# nucleo_jlink.net
KiCad netlist of a schematic drawn in EAGLE
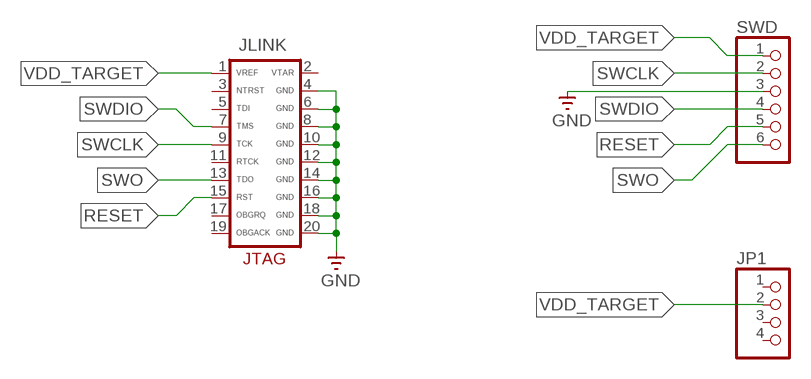
[diagram p0: schematic, sheet 1]

(export (version "E")
  (design (tool "Eeschema 10.0.6"))
  (components
    (comp (ref "JLINK")
      (value "JTAG-ARM")
      (footprint "eagle-import:JTAG-ARM")
      (libsource (lib "eagle-import") (part "JTAG-ARM"))
    )
    (comp (ref "JP1")
      (value "PINHD-1X4")
      (footprint "eagle-import:1X04")
      (libsource (lib "eagle-import") (part "PINHD-1X4"))
    )
    (comp (ref "SWD")
      (value "PINHD-1X6")
      (footprint "eagle-import:1X06")
      (libsource (lib "eagle-import") (part "PINHD-1X6"))
    )
  )
  (nets
    (net (code "1") (name "GND") (class "Default")
      (node (ref "JLINK") (pin "10") (pinfunction "GND_10") (pintype "passive"))
      (node (ref "JLINK") (pin "12") (pinfunction "GND_12") (pintype "passive"))
      (node (ref "JLINK") (pin "14") (pinfunction "GND_14") (pintype "passive"))
      (node (ref "JLINK") (pin "16") (pinfunction "GND_16") (pintype "passive"))
      (node (ref "JLINK") (pin "18") (pinfunction "GND_18") (pintype "passive"))
      (node (ref "JLINK") (pin "20") (pinfunction "GND_20") (pintype "passive"))
      (node (ref "JLINK") (pin "4") (pinfunction "GND_4") (pintype "passive"))
      (node (ref "JLINK") (pin "6") (pinfunction "GND_6") (pintype "passive"))
      (node (ref "JLINK") (pin "8") (pinfunction "GND_8") (pintype "passive"))
      (node (ref "SWD") (pin "3") (pinfunction "3_3") (pintype "passive"))
    )
    (net (code "2") (name "RESET") (class "Default")
      (node (ref "JLINK") (pin "15") (pinfunction "RST_15") (pintype "passive"))
      (node (ref "SWD") (pin "5") (pinfunction "5_5") (pintype "passive"))
    )
    (net (code "3") (name "SWCLK") (class "Default")
      (node (ref "JLINK") (pin "9") (pinfunction "TCK_9") (pintype "passive"))
      (node (ref "SWD") (pin "2") (pinfunction "2_2") (pintype "passive"))
    )
    (net (code "4") (name "SWDIO") (class "Default")
      (node (ref "JLINK") (pin "7") (pinfunction "TMS_7") (pintype "passive"))
      (node (ref "SWD") (pin "4") (pinfunction "4_4") (pintype "passive"))
    )
    (net (code "5") (name "SWO") (class "Default")
      (node (ref "JLINK") (pin "13") (pinfunction "TDO_13") (pintype "passive"))
      (node (ref "SWD") (pin "6") (pinfunction "6_6") (pintype "passive"))
    )
    (net (code "6") (name "VDD_TARGET") (class "Default")
      (node (ref "JLINK") (pin "1") (pinfunction "VREF_1") (pintype "passive"))
      (node (ref "JP1") (pin "2") (pinfunction "2_2") (pintype "passive"))
      (node (ref "SWD") (pin "1") (pinfunction "1_1") (pintype "passive"))
    )
    (net (code "7") (name "unconnected-(JLINK-NTRST-Pad3)") (class "Default")
      (node (ref "JLINK") (pin "3") (pinfunction "NTRST_3") (pintype "passive"))
    )
    (net (code "8") (name "unconnected-(JLINK-OBGACK-Pad19)") (class "Default")
      (node (ref "JLINK") (pin "19") (pinfunction "OBGACK_19") (pintype "passive"))
    )
    (net (code "9") (name "unconnected-(JLINK-OBGRQ-Pad17)") (class "Default")
      (node (ref "JLINK") (pin "17") (pinfunction "OBGRQ_17") (pintype "passive"))
    )
    (net (code "10") (name "unconnected-(JLINK-RTCK-Pad11)") (class "Default")
      (node (ref "JLINK") (pin "11") (pinfunction "RTCK_11") (pintype "passive"))
    )
    (net (code "11") (name "unconnected-(JLINK-TDI-Pad5)") (class "Default")
      (node (ref "JLINK") (pin "5") (pinfunction "TDI_5") (pintype "passive"))
    )
    (net (code "12") (name "unconnected-(JLINK-VTAR-Pad2)") (class "Default")
      (node (ref "JLINK") (pin "2") (pinfunction "VTAR_2") (pintype "passive"))
    )
    (net (code "13") (name "unconnected-(JP1-Pad1)") (class "Default")
      (node (ref "JP1") (pin "1") (pinfunction "1_1") (pintype "passive"))
    )
    (net (code "14") (name "unconnected-(JP1-Pad3)") (class "Default")
      (node (ref "JP1") (pin "3") (pinfunction "3_3") (pintype "passive"))
    )
    (net (code "15") (name "unconnected-(JP1-Pad4)") (class "Default")
      (node (ref "JP1") (pin "4") (pinfunction "4_4") (pintype "passive"))
    )
  )
)
